# FETS.net
KiCad netlist of a schematic drawn in Altium Designer
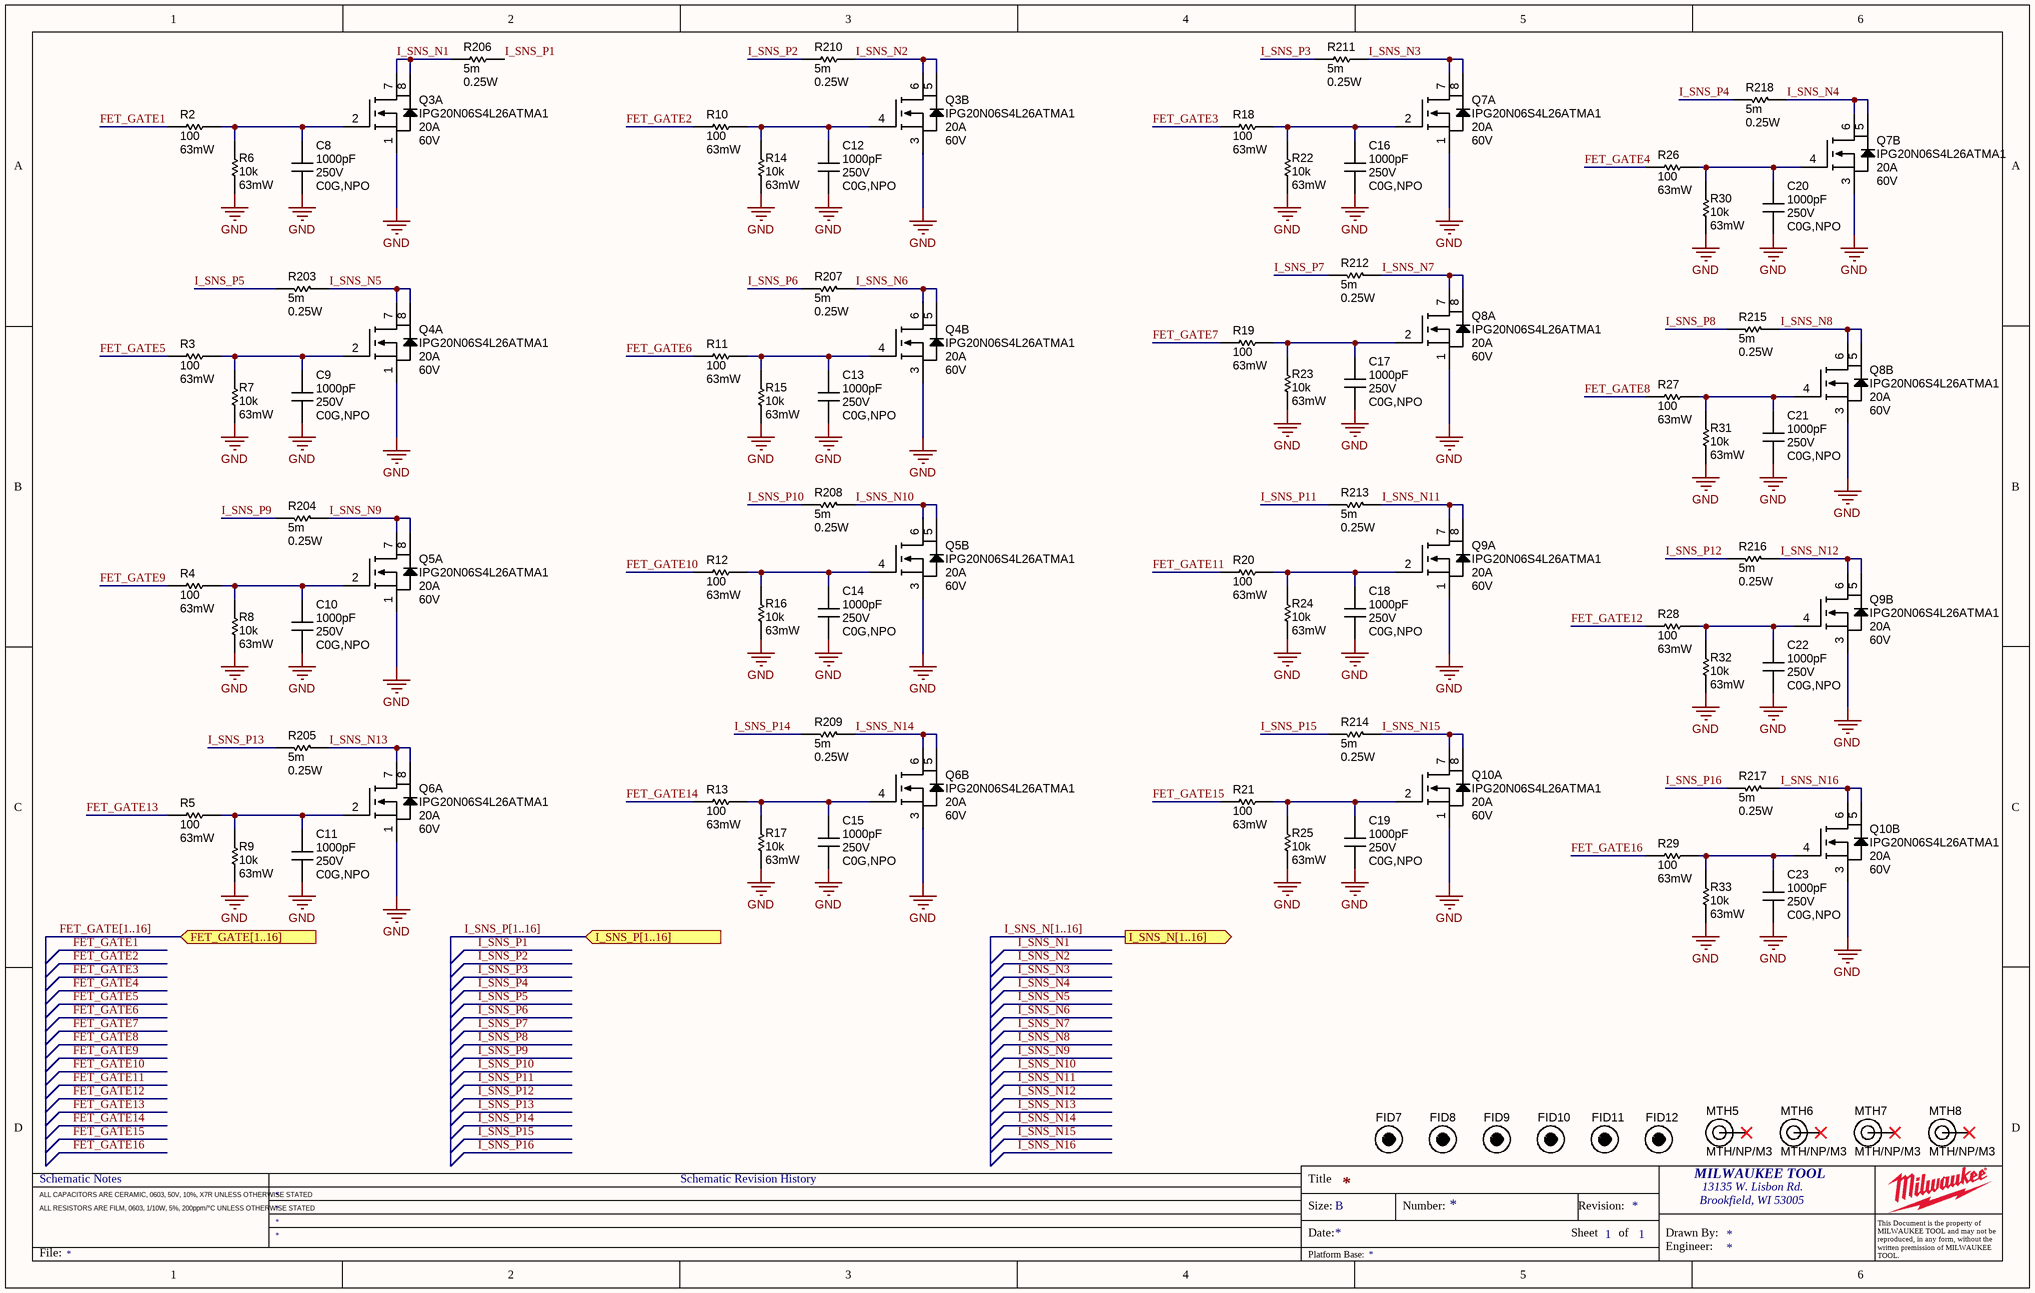
[diagram p0: FETS.SchDoc]

(export (version "E")
  (design (tool "Eeschema 10.0.6"))
  (components
    (comp (ref "C8")
      (value "1000pF")
      (footprint "CAPC1608X09N")
      (description "CAP CER 1000PF 250V X7R 0603")
      (fields
        (field (name "TOLERANCE") "5%")
        (field (name "MFR") "KEMET")
        (field (name "VOLTAGE RATING") "250V")
        (field (name "TEMP COEFF") "C0G,NPO")
      )
      (libsource (lib "General_Library") (part "CMP-004-0013"))
    )
    (comp (ref "C9")
      (value "1000pF")
      (footprint "CAPC1608X09N")
      (description "CAP CER 1000PF 250V X7R 0603")
      (fields
        (field (name "TOLERANCE") "5%")
        (field (name "MFR") "KEMET")
        (field (name "VOLTAGE RATING") "250V")
        (field (name "TEMP COEFF") "C0G,NPO")
      )
      (libsource (lib "General_Library") (part "CMP-004-0013"))
    )
    (comp (ref "C10")
      (value "1000pF")
      (footprint "CAPC1608X09N")
      (description "CAP CER 1000PF 250V X7R 0603")
      (fields
        (field (name "TOLERANCE") "5%")
        (field (name "MFR") "KEMET")
        (field (name "VOLTAGE RATING") "250V")
        (field (name "TEMP COEFF") "C0G,NPO")
      )
      (libsource (lib "General_Library") (part "CMP-004-0013"))
    )
    (comp (ref "C11")
      (value "1000pF")
      (footprint "CAPC1608X09N")
      (description "CAP CER 1000PF 250V X7R 0603")
      (fields
        (field (name "TOLERANCE") "5%")
        (field (name "MFR") "KEMET")
        (field (name "VOLTAGE RATING") "250V")
        (field (name "TEMP COEFF") "C0G,NPO")
      )
      (libsource (lib "General_Library") (part "CMP-004-0013"))
    )
    (comp (ref "C12")
      (value "1000pF")
      (footprint "CAPC1608X09N")
      (description "CAP CER 1000PF 250V X7R 0603")
      (fields
        (field (name "TOLERANCE") "5%")
        (field (name "MFR") "KEMET")
        (field (name "VOLTAGE RATING") "250V")
        (field (name "TEMP COEFF") "C0G,NPO")
      )
      (libsource (lib "General_Library") (part "CMP-004-0013"))
    )
    (comp (ref "C13")
      (value "1000pF")
      (footprint "CAPC1608X09N")
      (description "CAP CER 1000PF 250V X7R 0603")
      (fields
        (field (name "TOLERANCE") "5%")
        (field (name "MFR") "KEMET")
        (field (name "VOLTAGE RATING") "250V")
        (field (name "TEMP COEFF") "C0G,NPO")
      )
      (libsource (lib "General_Library") (part "CMP-004-0013"))
    )
    (comp (ref "C14")
      (value "1000pF")
      (footprint "CAPC1608X09N")
      (description "CAP CER 1000PF 250V X7R 0603")
      (fields
        (field (name "TOLERANCE") "5%")
        (field (name "MFR") "KEMET")
        (field (name "VOLTAGE RATING") "250V")
        (field (name "TEMP COEFF") "C0G,NPO")
      )
      (libsource (lib "General_Library") (part "CMP-004-0013"))
    )
    (comp (ref "C15")
      (value "1000pF")
      (footprint "CAPC1608X09N")
      (description "CAP CER 1000PF 250V X7R 0603")
      (fields
        (field (name "TOLERANCE") "5%")
        (field (name "MFR") "KEMET")
        (field (name "VOLTAGE RATING") "250V")
        (field (name "TEMP COEFF") "C0G,NPO")
      )
      (libsource (lib "General_Library") (part "CMP-004-0013"))
    )
    (comp (ref "C16")
      (value "1000pF")
      (footprint "CAPC1608X09N")
      (description "CAP CER 1000PF 250V X7R 0603")
      (fields
        (field (name "TOLERANCE") "5%")
        (field (name "MFR") "KEMET")
        (field (name "VOLTAGE RATING") "250V")
        (field (name "TEMP COEFF") "C0G,NPO")
      )
      (libsource (lib "General_Library") (part "CMP-004-0013"))
    )
    (comp (ref "C17")
      (value "1000pF")
      (footprint "CAPC1608X09N")
      (description "CAP CER 1000PF 250V X7R 0603")
      (fields
        (field (name "TOLERANCE") "5%")
        (field (name "MFR") "KEMET")
        (field (name "VOLTAGE RATING") "250V")
        (field (name "TEMP COEFF") "C0G,NPO")
      )
      (libsource (lib "General_Library") (part "CMP-004-0013"))
    )
    (comp (ref "C18")
      (value "1000pF")
      (footprint "CAPC1608X09N")
      (description "CAP CER 1000PF 250V X7R 0603")
      (fields
        (field (name "TOLERANCE") "5%")
        (field (name "MFR") "KEMET")
        (field (name "VOLTAGE RATING") "250V")
        (field (name "TEMP COEFF") "C0G,NPO")
      )
      (libsource (lib "General_Library") (part "CMP-004-0013"))
    )
    (comp (ref "C19")
      (value "1000pF")
      (footprint "CAPC1608X09N")
      (description "CAP CER 1000PF 250V X7R 0603")
      (fields
        (field (name "TOLERANCE") "5%")
        (field (name "MFR") "KEMET")
        (field (name "VOLTAGE RATING") "250V")
        (field (name "TEMP COEFF") "C0G,NPO")
      )
      (libsource (lib "General_Library") (part "CMP-004-0013"))
    )
    (comp (ref "C20")
      (value "1000pF")
      (footprint "CAPC1608X09N")
      (description "CAP CER 1000PF 250V X7R 0603")
      (fields
        (field (name "TOLERANCE") "5%")
        (field (name "MFR") "KEMET")
        (field (name "VOLTAGE RATING") "250V")
        (field (name "TEMP COEFF") "C0G,NPO")
      )
      (libsource (lib "General_Library") (part "CMP-004-0013"))
    )
    (comp (ref "C21")
      (value "1000pF")
      (footprint "CAPC1608X09N")
      (description "CAP CER 1000PF 250V X7R 0603")
      (fields
        (field (name "TOLERANCE") "5%")
        (field (name "MFR") "KEMET")
        (field (name "VOLTAGE RATING") "250V")
        (field (name "TEMP COEFF") "C0G,NPO")
      )
      (libsource (lib "General_Library") (part "CMP-004-0013"))
    )
    (comp (ref "C22")
      (value "1000pF")
      (footprint "CAPC1608X09N")
      (description "CAP CER 1000PF 250V X7R 0603")
      (fields
        (field (name "TOLERANCE") "5%")
        (field (name "MFR") "KEMET")
        (field (name "VOLTAGE RATING") "250V")
        (field (name "TEMP COEFF") "C0G,NPO")
      )
      (libsource (lib "General_Library") (part "CMP-004-0013"))
    )
    (comp (ref "C23")
      (value "1000pF")
      (footprint "CAPC1608X09N")
      (description "CAP CER 1000PF 250V X7R 0603")
      (fields
        (field (name "TOLERANCE") "5%")
        (field (name "MFR") "KEMET")
        (field (name "VOLTAGE RATING") "250V")
        (field (name "TEMP COEFF") "C0G,NPO")
      )
      (libsource (lib "General_Library") (part "CMP-004-0013"))
    )
    (comp (ref "FID7")
      (value "FIDUCIAL STANDARD")
      (footprint "FID")
      (description "STANDARD PCB FIDUCIAL")
      (libsource (lib "General_Library") (part "CMP-019-0003"))
    )
    (comp (ref "FID8")
      (value "FIDUCIAL STANDARD")
      (footprint "FID")
      (description "STANDARD PCB FIDUCIAL")
      (libsource (lib "General_Library") (part "CMP-019-0003"))
    )
    (comp (ref "FID9")
      (value "FIDUCIAL STANDARD")
      (footprint "FID")
      (description "STANDARD PCB FIDUCIAL")
      (libsource (lib "General_Library") (part "CMP-019-0003"))
    )
    (comp (ref "FID10")
      (value "FIDUCIAL STANDARD")
      (footprint "FID")
      (description "STANDARD PCB FIDUCIAL")
      (libsource (lib "General_Library") (part "CMP-019-0003"))
    )
    (comp (ref "FID11")
      (value "FIDUCIAL STANDARD")
      (footprint "FID")
      (description "STANDARD PCB FIDUCIAL")
      (libsource (lib "General_Library") (part "CMP-019-0003"))
    )
    (comp (ref "FID12")
      (value "FIDUCIAL STANDARD")
      (footprint "FID")
      (description "STANDARD PCB FIDUCIAL")
      (libsource (lib "General_Library") (part "CMP-019-0003"))
    )
    (comp (ref "MTH5")
      (value "MTH/NP/M3")
      (footprint "MTGNP700H325Z700P")
      (description "M3 Screw Mounted Hole Non-Plated")
      (libsource (lib "General_Library") (part "CMP-022-0003"))
    )
    (comp (ref "MTH6")
      (value "MTH/NP/M3")
      (footprint "MTGNP700H325Z700P")
      (description "M3 Screw Mounted Hole Non-Plated")
      (libsource (lib "General_Library") (part "CMP-022-0003"))
    )
    (comp (ref "MTH7")
      (value "MTH/NP/M3")
      (footprint "MTGNP700H325Z700P")
      (description "M3 Screw Mounted Hole Non-Plated")
      (libsource (lib "General_Library") (part "CMP-022-0003"))
    )
    (comp (ref "MTH8")
      (value "MTH/NP/M3")
      (footprint "MTGNP700H325Z700P")
      (description "M3 Screw Mounted Hole Non-Plated")
      (libsource (lib "General_Library") (part "CMP-022-0003"))
    )
    (comp (ref "Q3")
      (value "IPG20N06S4L26ATMA1")
      (footprint "INF-PG-TDSON-8-4")
      (description "MOSFET N-CH 25V 5.8A SOT23")
      (fields (field (name "MFR") "Infineon") (field (name "CURRENT") "20A") (field (name "VOLTAGE") "60V"))
      (libsource (lib "General_Library") (part "CMP-029-0047"))
    )
    (comp (ref "Q4")
      (value "IPG20N06S4L26ATMA1")
      (footprint "INF-PG-TDSON-8-4")
      (description "MOSFET N-CH 25V 5.8A SOT23")
      (fields (field (name "MFR") "Infineon") (field (name "CURRENT") "20A") (field (name "VOLTAGE") "60V"))
      (libsource (lib "General_Library") (part "CMP-029-0047"))
    )
    (comp (ref "Q5")
      (value "IPG20N06S4L26ATMA1")
      (footprint "INF-PG-TDSON-8-4")
      (description "MOSFET N-CH 25V 5.8A SOT23")
      (fields (field (name "MFR") "Infineon") (field (name "CURRENT") "20A") (field (name "VOLTAGE") "60V"))
      (libsource (lib "General_Library") (part "CMP-029-0047"))
    )
    (comp (ref "Q6")
      (value "IPG20N06S4L26ATMA1")
      (footprint "INF-PG-TDSON-8-4")
      (description "MOSFET N-CH 25V 5.8A SOT23")
      (fields (field (name "MFR") "Infineon") (field (name "CURRENT") "20A") (field (name "VOLTAGE") "60V"))
      (libsource (lib "General_Library") (part "CMP-029-0047"))
    )
    (comp (ref "Q7")
      (value "IPG20N06S4L26ATMA1")
      (footprint "INF-PG-TDSON-8-4")
      (description "MOSFET N-CH 25V 5.8A SOT23")
      (fields (field (name "MFR") "Infineon") (field (name "CURRENT") "20A") (field (name "VOLTAGE") "60V"))
      (libsource (lib "General_Library") (part "CMP-029-0047"))
    )
    (comp (ref "Q8")
      (value "IPG20N06S4L26ATMA1")
      (footprint "INF-PG-TDSON-8-4")
      (description "MOSFET N-CH 25V 5.8A SOT23")
      (fields (field (name "MFR") "Infineon") (field (name "CURRENT") "20A") (field (name "VOLTAGE") "60V"))
      (libsource (lib "General_Library") (part "CMP-029-0047"))
    )
    (comp (ref "Q9")
      (value "IPG20N06S4L26ATMA1")
      (footprint "INF-PG-TDSON-8-4")
      (description "MOSFET N-CH 25V 5.8A SOT23")
      (fields (field (name "MFR") "Infineon") (field (name "CURRENT") "20A") (field (name "VOLTAGE") "60V"))
      (libsource (lib "General_Library") (part "CMP-029-0047"))
    )
    (comp (ref "Q10")
      (value "IPG20N06S4L26ATMA1")
      (footprint "INF-PG-TDSON-8-4")
      (description "MOSFET N-CH 25V 5.8A SOT23")
      (fields (field (name "MFR") "Infineon") (field (name "CURRENT") "20A") (field (name "VOLTAGE") "60V"))
      (libsource (lib "General_Library") (part "CMP-029-0047"))
    )
    (comp (ref "R2")
      (value "100")
      (footprint "RESC1005X04N")
      (description "RES SMD 100 OHM 1% 1/16W 0402")
      (fields
        (field (name "TOLERANCE") "1%")
        (field (name "MFR") "Stackpole Electronics Inc")
        (field (name "WATTAGE") "63mW")
      )
      (libsource (lib "General_Library") (part "CMP-025-0156"))
    )
    (comp (ref "R3")
      (value "100")
      (footprint "RESC1005X04N")
      (description "RES SMD 100 OHM 1% 1/16W 0402")
      (fields
        (field (name "TOLERANCE") "1%")
        (field (name "MFR") "Stackpole Electronics Inc")
        (field (name "WATTAGE") "63mW")
      )
      (libsource (lib "General_Library") (part "CMP-025-0156"))
    )
    (comp (ref "R4")
      (value "100")
      (footprint "RESC1005X04N")
      (description "RES SMD 100 OHM 1% 1/16W 0402")
      (fields
        (field (name "TOLERANCE") "1%")
        (field (name "MFR") "Stackpole Electronics Inc")
        (field (name "WATTAGE") "63mW")
      )
      (libsource (lib "General_Library") (part "CMP-025-0156"))
    )
    (comp (ref "R5")
      (value "100")
      (footprint "RESC1005X04N")
      (description "RES SMD 100 OHM 1% 1/16W 0402")
      (fields
        (field (name "TOLERANCE") "1%")
        (field (name "MFR") "Stackpole Electronics Inc")
        (field (name "WATTAGE") "63mW")
      )
      (libsource (lib "General_Library") (part "CMP-025-0156"))
    )
    (comp (ref "R6")
      (value "10k")
      (footprint "RESC1005X04N")
      (description "RES SMD 10K OHM 0.5% 1/16W 0402")
      (fields
        (field (name "MFR") "Panasonic Electronic Components")
        (field (name "TOLERANCE") "0.5%")
        (field (name "WATTAGE") "63mW")
      )
      (libsource (lib "General_Library") (part "CMP-025-0026"))
    )
    (comp (ref "R7")
      (value "10k")
      (footprint "RESC1005X04N")
      (description "RES SMD 10K OHM 0.5% 1/16W 0402")
      (fields
        (field (name "MFR") "Panasonic Electronic Components")
        (field (name "TOLERANCE") "0.5%")
        (field (name "WATTAGE") "63mW")
      )
      (libsource (lib "General_Library") (part "CMP-025-0026"))
    )
    (comp (ref "R8")
      (value "10k")
      (footprint "RESC1005X04N")
      (description "RES SMD 10K OHM 0.5% 1/16W 0402")
      (fields
        (field (name "MFR") "Panasonic Electronic Components")
        (field (name "TOLERANCE") "0.5%")
        (field (name "WATTAGE") "63mW")
      )
      (libsource (lib "General_Library") (part "CMP-025-0026"))
    )
    (comp (ref "R9")
      (value "10k")
      (footprint "RESC1005X04N")
      (description "RES SMD 10K OHM 0.5% 1/16W 0402")
      (fields
        (field (name "MFR") "Panasonic Electronic Components")
        (field (name "TOLERANCE") "0.5%")
        (field (name "WATTAGE") "63mW")
      )
      (libsource (lib "General_Library") (part "CMP-025-0026"))
    )
    (comp (ref "R10")
      (value "100")
      (footprint "RESC1005X04N")
      (description "RES SMD 100 OHM 1% 1/16W 0402")
      (fields
        (field (name "TOLERANCE") "1%")
        (field (name "MFR") "Stackpole Electronics Inc")
        (field (name "WATTAGE") "63mW")
      )
      (libsource (lib "General_Library") (part "CMP-025-0156"))
    )
    (comp (ref "R11")
      (value "100")
      (footprint "RESC1005X04N")
      (description "RES SMD 100 OHM 1% 1/16W 0402")
      (fields
        (field (name "TOLERANCE") "1%")
        (field (name "MFR") "Stackpole Electronics Inc")
        (field (name "WATTAGE") "63mW")
      )
      (libsource (lib "General_Library") (part "CMP-025-0156"))
    )
    (comp (ref "R12")
      (value "100")
      (footprint "RESC1005X04N")
      (description "RES SMD 100 OHM 1% 1/16W 0402")
      (fields
        (field (name "TOLERANCE") "1%")
        (field (name "MFR") "Stackpole Electronics Inc")
        (field (name "WATTAGE") "63mW")
      )
      (libsource (lib "General_Library") (part "CMP-025-0156"))
    )
    (comp (ref "R13")
      (value "100")
      (footprint "RESC1005X04N")
      (description "RES SMD 100 OHM 1% 1/16W 0402")
      (fields
        (field (name "TOLERANCE") "1%")
        (field (name "MFR") "Stackpole Electronics Inc")
        (field (name "WATTAGE") "63mW")
      )
      (libsource (lib "General_Library") (part "CMP-025-0156"))
    )
    (comp (ref "R14")
      (value "10k")
      (footprint "RESC1005X04N")
      (description "RES SMD 10K OHM 0.5% 1/16W 0402")
      (fields
        (field (name "MFR") "Panasonic Electronic Components")
        (field (name "TOLERANCE") "0.5%")
        (field (name "WATTAGE") "63mW")
      )
      (libsource (lib "General_Library") (part "CMP-025-0026"))
    )
    (comp (ref "R15")
      (value "10k")
      (footprint "RESC1005X04N")
      (description "RES SMD 10K OHM 0.5% 1/16W 0402")
      (fields
        (field (name "MFR") "Panasonic Electronic Components")
        (field (name "TOLERANCE") "0.5%")
        (field (name "WATTAGE") "63mW")
      )
      (libsource (lib "General_Library") (part "CMP-025-0026"))
    )
    (comp (ref "R16")
      (value "10k")
      (footprint "RESC1005X04N")
      (description "RES SMD 10K OHM 0.5% 1/16W 0402")
      (fields
        (field (name "MFR") "Panasonic Electronic Components")
        (field (name "TOLERANCE") "0.5%")
        (field (name "WATTAGE") "63mW")
      )
      (libsource (lib "General_Library") (part "CMP-025-0026"))
    )
    (comp (ref "R17")
      (value "10k")
      (footprint "RESC1005X04N")
      (description "RES SMD 10K OHM 0.5% 1/16W 0402")
      (fields
        (field (name "MFR") "Panasonic Electronic Components")
        (field (name "TOLERANCE") "0.5%")
        (field (name "WATTAGE") "63mW")
      )
      (libsource (lib "General_Library") (part "CMP-025-0026"))
    )
    (comp (ref "R18")
      (value "100")
      (footprint "RESC1005X04N")
      (description "RES SMD 100 OHM 1% 1/16W 0402")
      (fields
        (field (name "TOLERANCE") "1%")
        (field (name "MFR") "Stackpole Electronics Inc")
        (field (name "WATTAGE") "63mW")
      )
      (libsource (lib "General_Library") (part "CMP-025-0156"))
    )
    (comp (ref "R19")
      (value "100")
      (footprint "RESC1005X04N")
      (description "RES SMD 100 OHM 1% 1/16W 0402")
      (fields
        (field (name "TOLERANCE") "1%")
        (field (name "MFR") "Stackpole Electronics Inc")
        (field (name "WATTAGE") "63mW")
      )
      (libsource (lib "General_Library") (part "CMP-025-0156"))
    )
    (comp (ref "R20")
      (value "100")
      (footprint "RESC1005X04N")
      (description "RES SMD 100 OHM 1% 1/16W 0402")
      (fields
        (field (name "TOLERANCE") "1%")
        (field (name "MFR") "Stackpole Electronics Inc")
        (field (name "WATTAGE") "63mW")
      )
      (libsource (lib "General_Library") (part "CMP-025-0156"))
    )
    (comp (ref "R21")
      (value "100")
      (footprint "RESC1005X04N")
      (description "RES SMD 100 OHM 1% 1/16W 0402")
      (fields
        (field (name "TOLERANCE") "1%")
        (field (name "MFR") "Stackpole Electronics Inc")
        (field (name "WATTAGE") "63mW")
      )
      (libsource (lib "General_Library") (part "CMP-025-0156"))
    )
    (comp (ref "R22")
      (value "10k")
      (footprint "RESC1005X04N")
      (description "RES SMD 10K OHM 0.5% 1/16W 0402")
      (fields
        (field (name "MFR") "Panasonic Electronic Components")
        (field (name "TOLERANCE") "0.5%")
        (field (name "WATTAGE") "63mW")
      )
      (libsource (lib "General_Library") (part "CMP-025-0026"))
    )
    (comp (ref "R23")
      (value "10k")
      (footprint "RESC1005X04N")
      (description "RES SMD 10K OHM 0.5% 1/16W 0402")
      (fields
        (field (name "MFR") "Panasonic Electronic Components")
        (field (name "TOLERANCE") "0.5%")
        (field (name "WATTAGE") "63mW")
      )
      (libsource (lib "General_Library") (part "CMP-025-0026"))
    )
    (comp (ref "R24")
      (value "10k")
      (footprint "RESC1005X04N")
      (description "RES SMD 10K OHM 0.5% 1/16W 0402")
      (fields
        (field (name "MFR") "Panasonic Electronic Components")
        (field (name "TOLERANCE") "0.5%")
        (field (name "WATTAGE") "63mW")
      )
      (libsource (lib "General_Library") (part "CMP-025-0026"))
    )
    (comp (ref "R25")
      (value "10k")
      (footprint "RESC1005X04N")
      (description "RES SMD 10K OHM 0.5% 1/16W 0402")
      (fields
        (field (name "MFR") "Panasonic Electronic Components")
        (field (name "TOLERANCE") "0.5%")
        (field (name "WATTAGE") "63mW")
      )
      (libsource (lib "General_Library") (part "CMP-025-0026"))
    )
    (comp (ref "R26")
      (value "100")
      (footprint "RESC1005X04N")
      (description "RES SMD 100 OHM 1% 1/16W 0402")
      (fields
        (field (name "TOLERANCE") "1%")
        (field (name "MFR") "Stackpole Electronics Inc")
        (field (name "WATTAGE") "63mW")
      )
      (libsource (lib "General_Library") (part "CMP-025-0156"))
    )
    (comp (ref "R27")
      (value "100")
      (footprint "RESC1005X04N")
      (description "RES SMD 100 OHM 1% 1/16W 0402")
      (fields
        (field (name "TOLERANCE") "1%")
        (field (name "MFR") "Stackpole Electronics Inc")
        (field (name "WATTAGE") "63mW")
      )
      (libsource (lib "General_Library") (part "CMP-025-0156"))
    )
    (comp (ref "R28")
      (value "100")
      (footprint "RESC1005X04N")
      (description "RES SMD 100 OHM 1% 1/16W 0402")
      (fields
        (field (name "TOLERANCE") "1%")
        (field (name "MFR") "Stackpole Electronics Inc")
        (field (name "WATTAGE") "63mW")
      )
      (libsource (lib "General_Library") (part "CMP-025-0156"))
    )
    (comp (ref "R29")
      (value "100")
      (footprint "RESC1005X04N")
      (description "RES SMD 100 OHM 1% 1/16W 0402")
      (fields
        (field (name "TOLERANCE") "1%")
        (field (name "MFR") "Stackpole Electronics Inc")
        (field (name "WATTAGE") "63mW")
      )
      (libsource (lib "General_Library") (part "CMP-025-0156"))
    )
    (comp (ref "R30")
      (value "10k")
      (footprint "RESC1005X04N")
      (description "RES SMD 10K OHM 0.5% 1/16W 0402")
      (fields
        (field (name "MFR") "Panasonic Electronic Components")
        (field (name "TOLERANCE") "0.5%")
        (field (name "WATTAGE") "63mW")
      )
      (libsource (lib "General_Library") (part "CMP-025-0026"))
    )
    (comp (ref "R31")
      (value "10k")
      (footprint "RESC1005X04N")
      (description "RES SMD 10K OHM 0.5% 1/16W 0402")
      (fields
        (field (name "MFR") "Panasonic Electronic Components")
        (field (name "TOLERANCE") "0.5%")
        (field (name "WATTAGE") "63mW")
      )
      (libsource (lib "General_Library") (part "CMP-025-0026"))
    )
    (comp (ref "R32")
      (value "10k")
      (footprint "RESC1005X04N")
      (description "RES SMD 10K OHM 0.5% 1/16W 0402")
      (fields
        (field (name "MFR") "Panasonic Electronic Components")
        (field (name "TOLERANCE") "0.5%")
        (field (name "WATTAGE") "63mW")
      )
      (libsource (lib "General_Library") (part "CMP-025-0026"))
    )
    (comp (ref "R33")
      (value "10k")
      (footprint "RESC1005X04N")
      (description "RES SMD 10K OHM 0.5% 1/16W 0402")
      (fields
        (field (name "MFR") "Panasonic Electronic Components")
        (field (name "TOLERANCE") "0.5%")
        (field (name "WATTAGE") "63mW")
      )
      (libsource (lib "General_Library") (part "CMP-025-0026"))
    )
    (comp (ref "R203")
      (value "5m")
      (footprint "RESC3115X07N")
      (description "RES SMD 5m OHM 1% 1/4W 1206")
      (fields (field (name "TOLERANCE") "1%") (field (name "MFR") "YAGEO") (field (name "WATTAGE") "0.25W"))
      (libsource (lib "General_Library") (part "CMP-025-0170"))
    )
    (comp (ref "R204")
      (value "5m")
      (footprint "RESC3115X07N")
      (description "RES SMD 5m OHM 1% 1/4W 1206")
      (fields (field (name "TOLERANCE") "1%") (field (name "MFR") "YAGEO") (field (name "WATTAGE") "0.25W"))
      (libsource (lib "General_Library") (part "CMP-025-0170"))
    )
    (comp (ref "R205")
      (value "5m")
      (footprint "RESC3115X07N")
      (description "RES SMD 5m OHM 1% 1/4W 1206")
      (fields (field (name "TOLERANCE") "1%") (field (name "MFR") "YAGEO") (field (name "WATTAGE") "0.25W"))
      (libsource (lib "General_Library") (part "CMP-025-0170"))
    )
    (comp (ref "R206")
      (value "5m")
      (footprint "RESC3115X07N")
      (description "RES SMD 5m OHM 1% 1/4W 1206")
      (fields (field (name "TOLERANCE") "1%") (field (name "MFR") "YAGEO") (field (name "WATTAGE") "0.25W"))
      (libsource (lib "General_Library") (part "CMP-025-0170"))
    )
    (comp (ref "R207")
      (value "5m")
      (footprint "RESC3115X07N")
      (description "RES SMD 5m OHM 1% 1/4W 1206")
      (fields (field (name "TOLERANCE") "1%") (field (name "MFR") "YAGEO") (field (name "WATTAGE") "0.25W"))
      (libsource (lib "General_Library") (part "CMP-025-0170"))
    )
    (comp (ref "R208")
      (value "5m")
      (footprint "RESC3115X07N")
      (description "RES SMD 5m OHM 1% 1/4W 1206")
      (fields (field (name "TOLERANCE") "1%") (field (name "MFR") "YAGEO") (field (name "WATTAGE") "0.25W"))
      (libsource (lib "General_Library") (part "CMP-025-0170"))
    )
    (comp (ref "R209")
      (value "5m")
      (footprint "RESC3115X07N")
      (description "RES SMD 5m OHM 1% 1/4W 1206")
      (fields (field (name "TOLERANCE") "1%") (field (name "MFR") "YAGEO") (field (name "WATTAGE") "0.25W"))
      (libsource (lib "General_Library") (part "CMP-025-0170"))
    )
    (comp (ref "R210")
      (value "5m")
      (footprint "RESC3115X07N")
      (description "RES SMD 5m OHM 1% 1/4W 1206")
      (fields (field (name "TOLERANCE") "1%") (field (name "MFR") "YAGEO") (field (name "WATTAGE") "0.25W"))
      (libsource (lib "General_Library") (part "CMP-025-0170"))
    )
    (comp (ref "R211")
      (value "5m")
      (footprint "RESC3115X07N")
      (description "RES SMD 5m OHM 1% 1/4W 1206")
      (fields (field (name "TOLERANCE") "1%") (field (name "MFR") "YAGEO") (field (name "WATTAGE") "0.25W"))
      (libsource (lib "General_Library") (part "CMP-025-0170"))
    )
    (comp (ref "R212")
      (value "5m")
      (footprint "RESC3115X07N")
      (description "RES SMD 5m OHM 1% 1/4W 1206")
      (fields (field (name "TOLERANCE") "1%") (field (name "MFR") "YAGEO") (field (name "WATTAGE") "0.25W"))
      (libsource (lib "General_Library") (part "CMP-025-0170"))
    )
    (comp (ref "R213")
      (value "5m")
      (footprint "RESC3115X07N")
      (description "RES SMD 5m OHM 1% 1/4W 1206")
      (fields (field (name "TOLERANCE") "1%") (field (name "MFR") "YAGEO") (field (name "WATTAGE") "0.25W"))
      (libsource (lib "General_Library") (part "CMP-025-0170"))
    )
    (comp (ref "R214")
      (value "5m")
      (footprint "RESC3115X07N")
      (description "RES SMD 5m OHM 1% 1/4W 1206")
      (fields (field (name "TOLERANCE") "1%") (field (name "MFR") "YAGEO") (field (name "WATTAGE") "0.25W"))
      (libsource (lib "General_Library") (part "CMP-025-0170"))
    )
    (comp (ref "R215")
      (value "5m")
      (footprint "RESC3115X07N")
      (description "RES SMD 5m OHM 1% 1/4W 1206")
      (fields (field (name "TOLERANCE") "1%") (field (name "MFR") "YAGEO") (field (name "WATTAGE") "0.25W"))
      (libsource (lib "General_Library") (part "CMP-025-0170"))
    )
    (comp (ref "R216")
      (value "5m")
      (footprint "RESC3115X07N")
      (description "RES SMD 5m OHM 1% 1/4W 1206")
      (fields (field (name "TOLERANCE") "1%") (field (name "MFR") "YAGEO") (field (name "WATTAGE") "0.25W"))
      (libsource (lib "General_Library") (part "CMP-025-0170"))
    )
    (comp (ref "R217")
      (value "5m")
      (footprint "RESC3115X07N")
      (description "RES SMD 5m OHM 1% 1/4W 1206")
      (fields (field (name "TOLERANCE") "1%") (field (name "MFR") "YAGEO") (field (name "WATTAGE") "0.25W"))
      (libsource (lib "General_Library") (part "CMP-025-0170"))
    )
    (comp (ref "R218")
      (value "5m")
      (footprint "RESC3115X07N")
      (description "RES SMD 5m OHM 1% 1/4W 1206")
      (fields (field (name "TOLERANCE") "1%") (field (name "MFR") "YAGEO") (field (name "WATTAGE") "0.25W"))
      (libsource (lib "General_Library") (part "CMP-025-0170"))
    )
  )
  (nets
    (net (code "1") (name "/FET_GATE1") (class "Default")
      (node (ref "R2") (pin "1") (pinfunction "1_1") (pintype "passive"))
    )
    (net (code "2") (name "/FET_GATE2") (class "Default")
      (node (ref "R10") (pin "1") (pinfunction "1_1") (pintype "passive"))
    )
    (net (code "3") (name "/FET_GATE3") (class "Default")
      (node (ref "R18") (pin "1") (pinfunction "1_1") (pintype "passive"))
    )
    (net (code "4") (name "/FET_GATE4") (class "Default")
      (node (ref "R26") (pin "1") (pinfunction "1_1") (pintype "passive"))
    )
    (net (code "5") (name "/FET_GATE5") (class "Default")
      (node (ref "R3") (pin "1") (pinfunction "1_1") (pintype "passive"))
    )
    (net (code "6") (name "/FET_GATE6") (class "Default")
      (node (ref "R11") (pin "1") (pinfunction "1_1") (pintype "passive"))
    )
    (net (code "7") (name "/FET_GATE7") (class "Default")
      (node (ref "R19") (pin "1") (pinfunction "1_1") (pintype "passive"))
    )
    (net (code "8") (name "/FET_GATE8") (class "Default")
      (node (ref "R27") (pin "1") (pinfunction "1_1") (pintype "passive"))
    )
    (net (code "9") (name "/FET_GATE9") (class "Default")
      (node (ref "R4") (pin "1") (pinfunction "1_1") (pintype "passive"))
    )
    (net (code "10") (name "/FET_GATE10") (class "Default")
      (node (ref "R12") (pin "1") (pinfunction "1_1") (pintype "passive"))
    )
    (net (code "11") (name "/FET_GATE11") (class "Default")
      (node (ref "R20") (pin "1") (pinfunction "1_1") (pintype "passive"))
    )
    (net (code "12") (name "/FET_GATE12") (class "Default")
      (node (ref "R28") (pin "1") (pinfunction "1_1") (pintype "passive"))
    )
    (net (code "13") (name "/FET_GATE13") (class "Default")
      (node (ref "R5") (pin "1") (pinfunction "1_1") (pintype "passive"))
    )
    (net (code "14") (name "/FET_GATE14") (class "Default")
      (node (ref "R13") (pin "1") (pinfunction "1_1") (pintype "passive"))
    )
    (net (code "15") (name "/FET_GATE15") (class "Default")
      (node (ref "R21") (pin "1") (pinfunction "1_1") (pintype "passive"))
    )
    (net (code "16") (name "/FET_GATE16") (class "Default")
      (node (ref "R29") (pin "1") (pinfunction "1_1") (pintype "passive"))
    )
    (net (code "18") (name "/I_SNS_N1") (class "Default")
      (node (ref "Q3") (pin "7") (pinfunction "D_7") (pintype "passive"))
      (node (ref "Q3") (pin "8") (pinfunction "D_8") (pintype "passive"))
      (node (ref "R206") (pin "1") (pinfunction "1_1") (pintype "passive"))
    )
    (net (code "19") (name "/I_SNS_N2") (class "Default")
      (node (ref "Q3") (pin "5") (pinfunction "D_5") (pintype "passive"))
      (node (ref "Q3") (pin "6") (pinfunction "D_6") (pintype "passive"))
      (node (ref "R210") (pin "2") (pinfunction "2_2") (pintype "passive"))
    )
    (net (code "20") (name "/I_SNS_N3") (class "Default")
      (node (ref "Q7") (pin "7") (pinfunction "D_7") (pintype "passive"))
      (node (ref "Q7") (pin "8") (pinfunction "D_8") (pintype "passive"))
      (node (ref "R211") (pin "2") (pinfunction "2_2") (pintype "passive"))
    )
    (net (code "21") (name "/I_SNS_N4") (class "Default")
      (node (ref "Q7") (pin "5") (pinfunction "D_5") (pintype "passive"))
      (node (ref "Q7") (pin "6") (pinfunction "D_6") (pintype "passive"))
      (node (ref "R218") (pin "1") (pinfunction "1_1") (pintype "passive"))
    )
    (net (code "22") (name "/I_SNS_N5") (class "Default")
      (node (ref "Q4") (pin "7") (pinfunction "D_7") (pintype "passive"))
      (node (ref "Q4") (pin "8") (pinfunction "D_8") (pintype "passive"))
      (node (ref "R203") (pin "1") (pinfunction "1_1") (pintype "passive"))
    )
    (net (code "23") (name "/I_SNS_N6") (class "Default")
      (node (ref "Q4") (pin "5") (pinfunction "D_5") (pintype "passive"))
      (node (ref "Q4") (pin "6") (pinfunction "D_6") (pintype "passive"))
      (node (ref "R207") (pin "1") (pinfunction "1_1") (pintype "passive"))
    )
    (net (code "24") (name "/I_SNS_N7") (class "Default")
      (node (ref "Q8") (pin "7") (pinfunction "D_7") (pintype "passive"))
      (node (ref "Q8") (pin "8") (pinfunction "D_8") (pintype "passive"))
      (node (ref "R212") (pin "1") (pinfunction "1_1") (pintype "passive"))
    )
    (net (code "25") (name "/I_SNS_N8") (class "Default")
      (node (ref "Q8") (pin "5") (pinfunction "D_5") (pintype "passive"))
      (node (ref "Q8") (pin "6") (pinfunction "D_6") (pintype "passive"))
      (node (ref "R215") (pin "1") (pinfunction "1_1") (pintype "passive"))
    )
    (net (code "26") (name "/I_SNS_N9") (class "Default")
      (node (ref "Q5") (pin "7") (pinfunction "D_7") (pintype "passive"))
      (node (ref "Q5") (pin "8") (pinfunction "D_8") (pintype "passive"))
      (node (ref "R204") (pin "1") (pinfunction "1_1") (pintype "passive"))
    )
    (net (code "27") (name "/I_SNS_N10") (class "Default")
      (node (ref "Q5") (pin "5") (pinfunction "D_5") (pintype "passive"))
      (node (ref "Q5") (pin "6") (pinfunction "D_6") (pintype "passive"))
      (node (ref "R208") (pin "1") (pinfunction "1_1") (pintype "passive"))
    )
    (net (code "28") (name "/I_SNS_N11") (class "Default")
      (node (ref "Q9") (pin "7") (pinfunction "D_7") (pintype "passive"))
      (node (ref "Q9") (pin "8") (pinfunction "D_8") (pintype "passive"))
      (node (ref "R213") (pin "1") (pinfunction "1_1") (pintype "passive"))
    )
    (net (code "29") (name "/I_SNS_N12") (class "Default")
      (node (ref "Q9") (pin "5") (pinfunction "D_5") (pintype "passive"))
      (node (ref "Q9") (pin "6") (pinfunction "D_6") (pintype "passive"))
      (node (ref "R216") (pin "1") (pinfunction "1_1") (pintype "passive"))
    )
    (net (code "30") (name "/I_SNS_N13") (class "Default")
      (node (ref "Q6") (pin "7") (pinfunction "D_7") (pintype "passive"))
      (node (ref "Q6") (pin "8") (pinfunction "D_8") (pintype "passive"))
      (node (ref "R205") (pin "1") (pinfunction "1_1") (pintype "passive"))
    )
    (net (code "31") (name "/I_SNS_N14") (class "Default")
      (node (ref "Q6") (pin "5") (pinfunction "D_5") (pintype "passive"))
      (node (ref "Q6") (pin "6") (pinfunction "D_6") (pintype "passive"))
      (node (ref "R209") (pin "1") (pinfunction "1_1") (pintype "passive"))
    )
    (net (code "32") (name "/I_SNS_N15") (class "Default")
      (node (ref "Q10") (pin "7") (pinfunction "D_7") (pintype "passive"))
      (node (ref "Q10") (pin "8") (pinfunction "D_8") (pintype "passive"))
      (node (ref "R214") (pin "1") (pinfunction "1_1") (pintype "passive"))
    )
    (net (code "33") (name "/I_SNS_N16") (class "Default")
      (node (ref "Q10") (pin "5") (pinfunction "D_5") (pintype "passive"))
      (node (ref "Q10") (pin "6") (pinfunction "D_6") (pintype "passive"))
      (node (ref "R217") (pin "1") (pinfunction "1_1") (pintype "passive"))
    )
    (net (code "35") (name "/I_SNS_P1") (class "Default")
      (node (ref "R206") (pin "2") (pinfunction "2_2") (pintype "passive"))
    )
    (net (code "36") (name "/I_SNS_P2") (class "Default")
      (node (ref "R210") (pin "1") (pinfunction "1_1") (pintype "passive"))
    )
    (net (code "37") (name "/I_SNS_P3") (class "Default")
      (node (ref "R211") (pin "1") (pinfunction "1_1") (pintype "passive"))
    )
    (net (code "38") (name "/I_SNS_P4") (class "Default")
      (node (ref "R218") (pin "2") (pinfunction "2_2") (pintype "passive"))
    )
    (net (code "39") (name "/I_SNS_P5") (class "Default")
      (node (ref "R203") (pin "2") (pinfunction "2_2") (pintype "passive"))
    )
    (net (code "40") (name "/I_SNS_P6") (class "Default")
      (node (ref "R207") (pin "2") (pinfunction "2_2") (pintype "passive"))
    )
    (net (code "41") (name "/I_SNS_P7") (class "Default")
      (node (ref "R212") (pin "2") (pinfunction "2_2") (pintype "passive"))
    )
    (net (code "42") (name "/I_SNS_P8") (class "Default")
      (node (ref "R215") (pin "2") (pinfunction "2_2") (pintype "passive"))
    )
    (net (code "43") (name "/I_SNS_P9") (class "Default")
      (node (ref "R204") (pin "2") (pinfunction "2_2") (pintype "passive"))
    )
    (net (code "44") (name "/I_SNS_P10") (class "Default")
      (node (ref "R208") (pin "2") (pinfunction "2_2") (pintype "passive"))
    )
    (net (code "45") (name "/I_SNS_P11") (class "Default")
      (node (ref "R213") (pin "2") (pinfunction "2_2") (pintype "passive"))
    )
    (net (code "46") (name "/I_SNS_P12") (class "Default")
      (node (ref "R216") (pin "2") (pinfunction "2_2") (pintype "passive"))
    )
    (net (code "47") (name "/I_SNS_P13") (class "Default")
      (node (ref "R205") (pin "2") (pinfunction "2_2") (pintype "passive"))
    )
    (net (code "48") (name "/I_SNS_P14") (class "Default")
      (node (ref "R209") (pin "2") (pinfunction "2_2") (pintype "passive"))
    )
    (net (code "49") (name "/I_SNS_P15") (class "Default")
      (node (ref "R214") (pin "2") (pinfunction "2_2") (pintype "passive"))
    )
    (net (code "50") (name "/I_SNS_P16") (class "Default")
      (node (ref "R217") (pin "2") (pinfunction "2_2") (pintype "passive"))
    )
    (net (code "52") (name "GND") (class "Default")
      (node (ref "C10") (pin "2") (pinfunction "2_2") (pintype "passive"))
      (node (ref "C11") (pin "2") (pinfunction "2_2") (pintype "passive"))
      (node (ref "C12") (pin "2") (pinfunction "2_2") (pintype "passive"))
      (node (ref "C13") (pin "2") (pinfunction "2_2") (pintype "passive"))
      (node (ref "C14") (pin "2") (pinfunction "2_2") (pintype "passive"))
      (node (ref "C15") (pin "2") (pinfunction "2_2") (pintype "passive"))
      (node (ref "C16") (pin "2") (pinfunction "2_2") (pintype "passive"))
      (node (ref "C17") (pin "2") (pinfunction "2_2") (pintype "passive"))
      (node (ref "C18") (pin "2") (pinfunction "2_2") (pintype "passive"))
      (node (ref "C19") (pin "2") (pinfunction "2_2") (pintype "passive"))
      (node (ref "C20") (pin "2") (pinfunction "2_2") (pintype "passive"))
      (node (ref "C21") (pin "2") (pinfunction "2_2") (pintype "passive"))
      (node (ref "C22") (pin "2") (pinfunction "2_2") (pintype "passive"))
      (node (ref "C23") (pin "2") (pinfunction "2_2") (pintype "passive"))
      (node (ref "C8") (pin "2") (pinfunction "2_2") (pintype "passive"))
      (node (ref "C9") (pin "2") (pinfunction "2_2") (pintype "passive"))
      (node (ref "Q10") (pin "1") (pinfunction "S_1") (pintype "passive"))
      (node (ref "Q10") (pin "3") (pinfunction "S_3") (pintype "passive"))
      (node (ref "Q3") (pin "1") (pinfunction "S_1") (pintype "passive"))
      (node (ref "Q3") (pin "3") (pinfunction "S_3") (pintype "passive"))
      (node (ref "Q4") (pin "1") (pinfunction "S_1") (pintype "passive"))
      (node (ref "Q4") (pin "3") (pinfunction "S_3") (pintype "passive"))
      (node (ref "Q5") (pin "1") (pinfunction "S_1") (pintype "passive"))
      (node (ref "Q5") (pin "3") (pinfunction "S_3") (pintype "passive"))
      (node (ref "Q6") (pin "1") (pinfunction "S_1") (pintype "passive"))
      (node (ref "Q6") (pin "3") (pinfunction "S_3") (pintype "passive"))
      (node (ref "Q7") (pin "1") (pinfunction "S_1") (pintype "passive"))
      (node (ref "Q7") (pin "3") (pinfunction "S_3") (pintype "passive"))
      (node (ref "Q8") (pin "1") (pinfunction "S_1") (pintype "passive"))
      (node (ref "Q8") (pin "3") (pinfunction "S_3") (pintype "passive"))
      (node (ref "Q9") (pin "1") (pinfunction "S_1") (pintype "passive"))
      (node (ref "Q9") (pin "3") (pinfunction "S_3") (pintype "passive"))
      (node (ref "R14") (pin "1") (pinfunction "1_1") (pintype "passive"))
      (node (ref "R15") (pin "1") (pinfunction "1_1") (pintype "passive"))
      (node (ref "R16") (pin "1") (pinfunction "1_1") (pintype "passive"))
      (node (ref "R17") (pin "1") (pinfunction "1_1") (pintype "passive"))
      (node (ref "R22") (pin "1") (pinfunction "1_1") (pintype "passive"))
      (node (ref "R23") (pin "1") (pinfunction "1_1") (pintype "passive"))
      (node (ref "R24") (pin "1") (pinfunction "1_1") (pintype "passive"))
      (node (ref "R25") (pin "1") (pinfunction "1_1") (pintype "passive"))
      (node (ref "R30") (pin "1") (pinfunction "1_1") (pintype "passive"))
      (node (ref "R31") (pin "1") (pinfunction "1_1") (pintype "passive"))
      (node (ref "R32") (pin "1") (pinfunction "1_1") (pintype "passive"))
      (node (ref "R33") (pin "1") (pinfunction "1_1") (pintype "passive"))
      (node (ref "R6") (pin "1") (pinfunction "1_1") (pintype "passive"))
      (node (ref "R7") (pin "1") (pinfunction "1_1") (pintype "passive"))
      (node (ref "R8") (pin "1") (pinfunction "1_1") (pintype "passive"))
      (node (ref "R9") (pin "1") (pinfunction "1_1") (pintype "passive"))
    )
    (net (code "53") (name "Net-(Q3A-G)") (class "Default")
      (node (ref "C8") (pin "1") (pinfunction "1_1") (pintype "passive"))
      (node (ref "Q3") (pin "2") (pinfunction "G_2") (pintype "passive"))
      (node (ref "R2") (pin "2") (pinfunction "2_2") (pintype "passive"))
      (node (ref "R6") (pin "2") (pinfunction "2_2") (pintype "passive"))
    )
    (net (code "54") (name "Net-(Q3B-G)") (class "Default")
      (node (ref "C12") (pin "1") (pinfunction "1_1") (pintype "passive"))
      (node (ref "Q3") (pin "4") (pinfunction "G_4") (pintype "passive"))
      (node (ref "R10") (pin "2") (pinfunction "2_2") (pintype "passive"))
      (node (ref "R14") (pin "2") (pinfunction "2_2") (pintype "passive"))
    )
    (net (code "55") (name "Net-(Q4A-G)") (class "Default")
      (node (ref "C9") (pin "1") (pinfunction "1_1") (pintype "passive"))
      (node (ref "Q4") (pin "2") (pinfunction "G_2") (pintype "passive"))
      (node (ref "R3") (pin "2") (pinfunction "2_2") (pintype "passive"))
      (node (ref "R7") (pin "2") (pinfunction "2_2") (pintype "passive"))
    )
    (net (code "56") (name "Net-(Q4B-G)") (class "Default")
      (node (ref "C13") (pin "1") (pinfunction "1_1") (pintype "passive"))
      (node (ref "Q4") (pin "4") (pinfunction "G_4") (pintype "passive"))
      (node (ref "R11") (pin "2") (pinfunction "2_2") (pintype "passive"))
      (node (ref "R15") (pin "2") (pinfunction "2_2") (pintype "passive"))
    )
    (net (code "57") (name "Net-(Q5A-G)") (class "Default")
      (node (ref "C10") (pin "1") (pinfunction "1_1") (pintype "passive"))
      (node (ref "Q5") (pin "2") (pinfunction "G_2") (pintype "passive"))
      (node (ref "R4") (pin "2") (pinfunction "2_2") (pintype "passive"))
      (node (ref "R8") (pin "2") (pinfunction "2_2") (pintype "passive"))
    )
    (net (code "58") (name "Net-(Q5B-G)") (class "Default")
      (node (ref "C14") (pin "1") (pinfunction "1_1") (pintype "passive"))
      (node (ref "Q5") (pin "4") (pinfunction "G_4") (pintype "passive"))
      (node (ref "R12") (pin "2") (pinfunction "2_2") (pintype "passive"))
      (node (ref "R16") (pin "2") (pinfunction "2_2") (pintype "passive"))
    )
    (net (code "59") (name "Net-(Q6A-G)") (class "Default")
      (node (ref "C11") (pin "1") (pinfunction "1_1") (pintype "passive"))
      (node (ref "Q6") (pin "2") (pinfunction "G_2") (pintype "passive"))
      (node (ref "R5") (pin "2") (pinfunction "2_2") (pintype "passive"))
      (node (ref "R9") (pin "2") (pinfunction "2_2") (pintype "passive"))
    )
    (net (code "60") (name "Net-(Q6B-G)") (class "Default")
      (node (ref "C15") (pin "1") (pinfunction "1_1") (pintype "passive"))
      (node (ref "Q6") (pin "4") (pinfunction "G_4") (pintype "passive"))
      (node (ref "R13") (pin "2") (pinfunction "2_2") (pintype "passive"))
      (node (ref "R17") (pin "2") (pinfunction "2_2") (pintype "passive"))
    )
    (net (code "61") (name "Net-(Q7A-G)") (class "Default")
      (node (ref "C16") (pin "1") (pinfunction "1_1") (pintype "passive"))
      (node (ref "Q7") (pin "2") (pinfunction "G_2") (pintype "passive"))
      (node (ref "R18") (pin "2") (pinfunction "2_2") (pintype "passive"))
      (node (ref "R22") (pin "2") (pinfunction "2_2") (pintype "passive"))
    )
    (net (code "62") (name "Net-(Q7B-G)") (class "Default")
      (node (ref "C20") (pin "1") (pinfunction "1_1") (pintype "passive"))
      (node (ref "Q7") (pin "4") (pinfunction "G_4") (pintype "passive"))
      (node (ref "R26") (pin "2") (pinfunction "2_2") (pintype "passive"))
      (node (ref "R30") (pin "2") (pinfunction "2_2") (pintype "passive"))
    )
    (net (code "63") (name "Net-(Q8A-G)") (class "Default")
      (node (ref "C17") (pin "1") (pinfunction "1_1") (pintype "passive"))
      (node (ref "Q8") (pin "2") (pinfunction "G_2") (pintype "passive"))
      (node (ref "R19") (pin "2") (pinfunction "2_2") (pintype "passive"))
      (node (ref "R23") (pin "2") (pinfunction "2_2") (pintype "passive"))
    )
    (net (code "64") (name "Net-(Q8B-G)") (class "Default")
      (node (ref "C21") (pin "1") (pinfunction "1_1") (pintype "passive"))
      (node (ref "Q8") (pin "4") (pinfunction "G_4") (pintype "passive"))
      (node (ref "R27") (pin "2") (pinfunction "2_2") (pintype "passive"))
      (node (ref "R31") (pin "2") (pinfunction "2_2") (pintype "passive"))
    )
    (net (code "65") (name "Net-(Q9A-G)") (class "Default")
      (node (ref "C18") (pin "1") (pinfunction "1_1") (pintype "passive"))
      (node (ref "Q9") (pin "2") (pinfunction "G_2") (pintype "passive"))
      (node (ref "R20") (pin "2") (pinfunction "2_2") (pintype "passive"))
      (node (ref "R24") (pin "2") (pinfunction "2_2") (pintype "passive"))
    )
    (net (code "66") (name "Net-(Q9B-G)") (class "Default")
      (node (ref "C22") (pin "1") (pinfunction "1_1") (pintype "passive"))
      (node (ref "Q9") (pin "4") (pinfunction "G_4") (pintype "passive"))
      (node (ref "R28") (pin "2") (pinfunction "2_2") (pintype "passive"))
      (node (ref "R32") (pin "2") (pinfunction "2_2") (pintype "passive"))
    )
    (net (code "67") (name "Net-(Q10A-G)") (class "Default")
      (node (ref "C19") (pin "1") (pinfunction "1_1") (pintype "passive"))
      (node (ref "Q10") (pin "2") (pinfunction "G_2") (pintype "passive"))
      (node (ref "R21") (pin "2") (pinfunction "2_2") (pintype "passive"))
      (node (ref "R25") (pin "2") (pinfunction "2_2") (pintype "passive"))
    )
    (net (code "68") (name "Net-(Q10B-G)") (class "Default")
      (node (ref "C23") (pin "1") (pinfunction "1_1") (pintype "passive"))
      (node (ref "Q10") (pin "4") (pinfunction "G_4") (pintype "passive"))
      (node (ref "R29") (pin "2") (pinfunction "2_2") (pintype "passive"))
      (node (ref "R33") (pin "2") (pinfunction "2_2") (pintype "passive"))
    )
    (net (code "69") (name "unconnected-(MTH5-Pad1)") (class "Default")
      (node (ref "MTH5") (pin "1") (pinfunction "1_1") (pintype "passive+no_connect"))
    )
    (net (code "70") (name "unconnected-(MTH6-Pad1)") (class "Default")
      (node (ref "MTH6") (pin "1") (pinfunction "1_1") (pintype "passive+no_connect"))
    )
    (net (code "71") (name "unconnected-(MTH7-Pad1)") (class "Default")
      (node (ref "MTH7") (pin "1") (pinfunction "1_1") (pintype "passive+no_connect"))
    )
    (net (code "72") (name "unconnected-(MTH8-Pad1)") (class "Default")
      (node (ref "MTH8") (pin "1") (pinfunction "1_1") (pintype "passive+no_connect"))
    )
  )
)
